# Power.net
KiCad netlist of a schematic drawn in Altium Designer
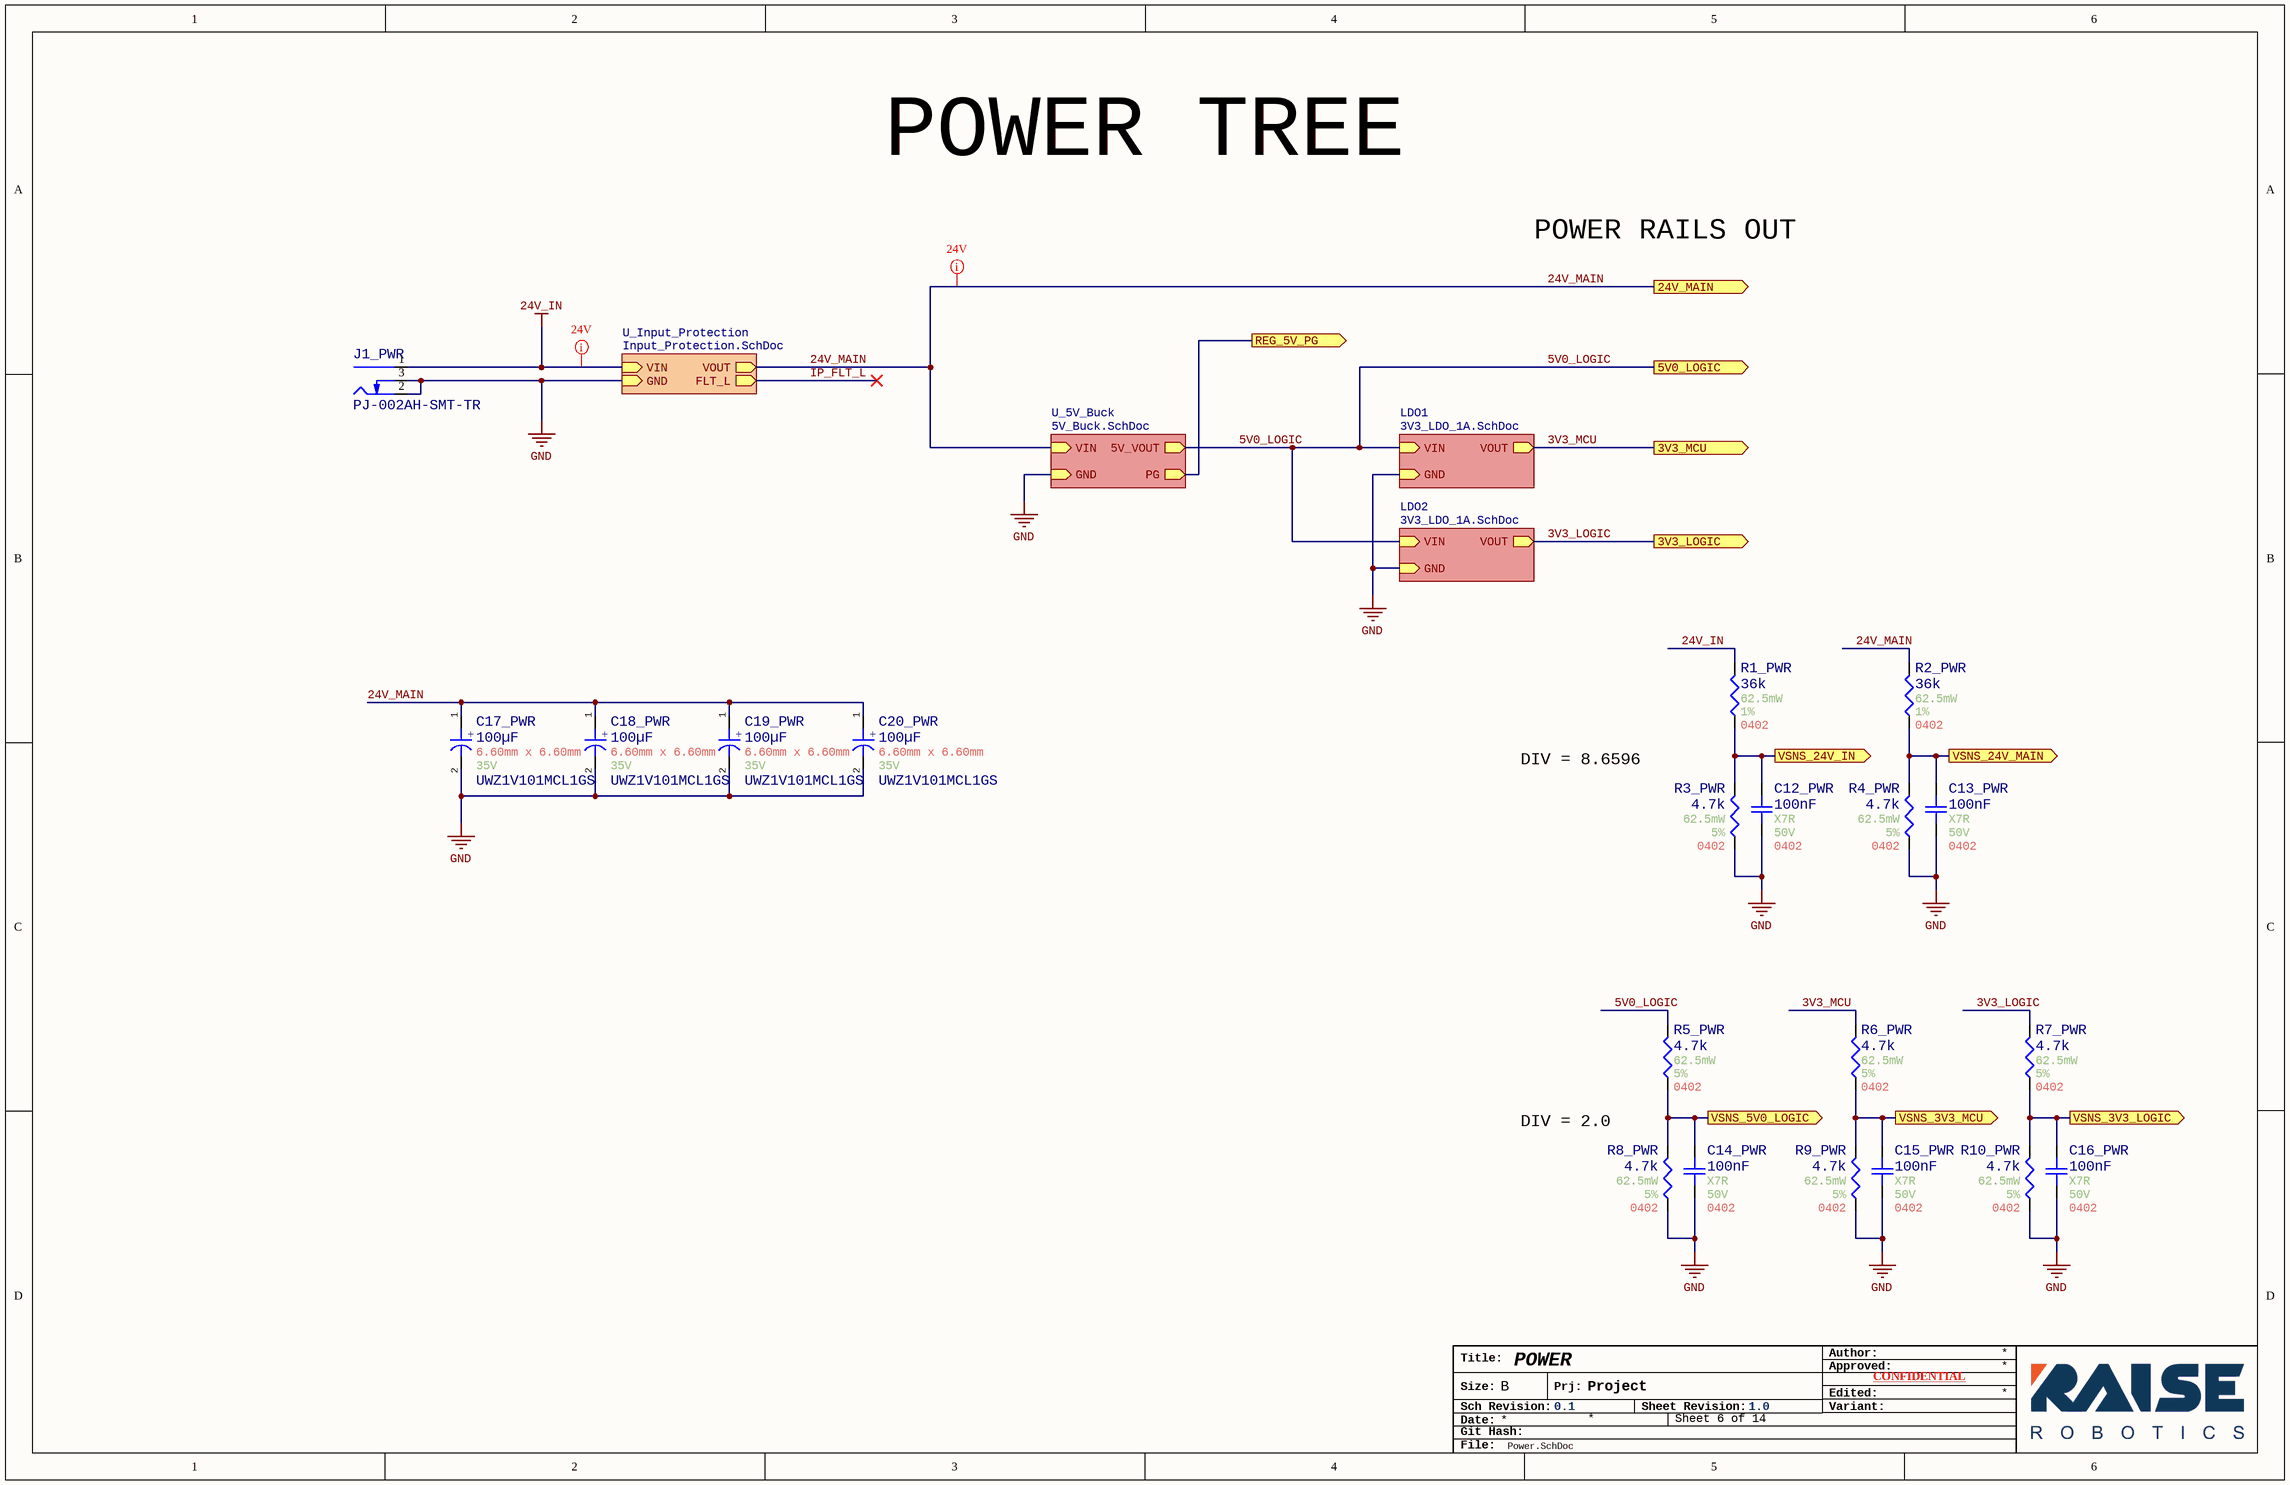
[diagram p0: Power.SchDoc]

(export (version "E")
  (design (tool "Eeschema 10.0.6"))
  (components
    (comp (ref "C12_PWR")
      (value "100nF")
      (footprint "Generic 0402 capacitor")
      (fields
        (field (name "TEMPERATURE COEFFICIENT") "X7R")
        (field (name "VOLTAGE RATING") "50V")
        (field (name "CASE/PACKAGE") "0402")
        (field (name "TOLERANCE") "10%")
        (field (name "Comment") "GRT155R71H104KE01D")
      )
      (libsource (lib "Raise Robotics") (part "Unpolarized Capacitor"))
    )
    (comp (ref "C13_PWR")
      (value "100nF")
      (footprint "Generic 0402 capacitor")
      (fields
        (field (name "TEMPERATURE COEFFICIENT") "X7R")
        (field (name "VOLTAGE RATING") "50V")
        (field (name "CASE/PACKAGE") "0402")
        (field (name "TOLERANCE") "10%")
        (field (name "Comment") "GRT155R71H104KE01D")
      )
      (libsource (lib "Raise Robotics") (part "Unpolarized Capacitor"))
    )
    (comp (ref "C14_PWR")
      (value "100nF")
      (footprint "Generic 0402 capacitor")
      (fields
        (field (name "TEMPERATURE COEFFICIENT") "X7R")
        (field (name "VOLTAGE RATING") "50V")
        (field (name "CASE/PACKAGE") "0402")
        (field (name "TOLERANCE") "10%")
        (field (name "Comment") "GRT155R71H104KE01D")
      )
      (libsource (lib "Raise Robotics") (part "Unpolarized Capacitor"))
    )
    (comp (ref "C15_PWR")
      (value "100nF")
      (footprint "Generic 0402 capacitor")
      (fields
        (field (name "TEMPERATURE COEFFICIENT") "X7R")
        (field (name "VOLTAGE RATING") "50V")
        (field (name "CASE/PACKAGE") "0402")
        (field (name "TOLERANCE") "10%")
        (field (name "Comment") "GRT155R71H104KE01D")
      )
      (libsource (lib "Raise Robotics") (part "Unpolarized Capacitor"))
    )
    (comp (ref "C16_PWR")
      (value "100nF")
      (footprint "Generic 0402 capacitor")
      (fields
        (field (name "TEMPERATURE COEFFICIENT") "X7R")
        (field (name "VOLTAGE RATING") "50V")
        (field (name "CASE/PACKAGE") "0402")
        (field (name "TOLERANCE") "10%")
        (field (name "Comment") "GRT155R71H104KE01D")
      )
      (libsource (lib "Raise Robotics") (part "Unpolarized Capacitor"))
    )
    (comp (ref "C17_PWR")
      (value "UWZ1V101MCL1GS")
      (footprint "UWZ1V101MCL1GS")
      (fields
        (field (name "ALTIUM_VALUE") "100µF")
        (field (name "CASE/PACKAGE") "6.60mm x 6.60mm")
        (field (name "VOLTAGE RATING") "35V")
      )
      (libsource (lib "Raise Robotics") (part "Polarized Capacitor Pin1+"))
    )
    (comp (ref "C18_PWR")
      (value "UWZ1V101MCL1GS")
      (footprint "UWZ1V101MCL1GS")
      (fields
        (field (name "ALTIUM_VALUE") "100µF")
        (field (name "CASE/PACKAGE") "6.60mm x 6.60mm")
        (field (name "VOLTAGE RATING") "35V")
      )
      (libsource (lib "Raise Robotics") (part "Polarized Capacitor Pin1+"))
    )
    (comp (ref "C19_PWR")
      (value "UWZ1V101MCL1GS")
      (footprint "UWZ1V101MCL1GS")
      (fields
        (field (name "ALTIUM_VALUE") "100µF")
        (field (name "CASE/PACKAGE") "6.60mm x 6.60mm")
        (field (name "VOLTAGE RATING") "35V")
      )
      (libsource (lib "Raise Robotics") (part "Polarized Capacitor Pin1+"))
    )
    (comp (ref "C20_PWR")
      (value "UWZ1V101MCL1GS")
      (footprint "UWZ1V101MCL1GS")
      (fields
        (field (name "ALTIUM_VALUE") "100µF")
        (field (name "CASE/PACKAGE") "6.60mm x 6.60mm")
        (field (name "VOLTAGE RATING") "35V")
      )
      (libsource (lib "Raise Robotics") (part "Polarized Capacitor Pin1+"))
    )
    (comp (ref "J1_PWR")
      (value "PJ-002AH-SMT-TR")
      (footprint "CUI PJ-002AH-SMT-TR")
      (description "CONN PWR JACK 2X5.5MM SOLDER")
      (fields (field (name "MANUFACTURER") "CUI Devices"))
      (libsource (lib "Celestial Altium Library - altium_library") (part "Barrel Connector"))
    )
    (comp (ref "R1_PWR")
      (value "36k")
      (footprint "Generic 0402 Resistor")
      (fields
        (field (name "POWER") "62.5mW")
        (field (name "TOLERANCE") "1%")
        (field (name "CASE/PACKAGE") "0402")
        (field (name "Comment") "AC0402FR-0736KL")
      )
      (libsource (lib "Raise Robotics") (part "Resistor"))
    )
    (comp (ref "R2_PWR")
      (value "36k")
      (footprint "Generic 0402 Resistor")
      (fields
        (field (name "POWER") "62.5mW")
        (field (name "TOLERANCE") "1%")
        (field (name "CASE/PACKAGE") "0402")
        (field (name "Comment") "AC0402FR-0736KL")
      )
      (libsource (lib "Raise Robotics") (part "Resistor"))
    )
    (comp (ref "R3_PWR")
      (value "4.7k")
      (footprint "Generic 0402 Resistor")
      (fields
        (field (name "POWER") "62.5mW")
        (field (name "TOLERANCE") "5%")
        (field (name "CASE/PACKAGE") "0402")
        (field (name "MANUFACTURER PART NUMBER") "Blank")
        (field (name "Comment") "WR04X472JTL")
      )
      (libsource (lib "Raise Robotics") (part "Resistor"))
    )
    (comp (ref "R4_PWR")
      (value "4.7k")
      (footprint "Generic 0402 Resistor")
      (fields
        (field (name "POWER") "62.5mW")
        (field (name "TOLERANCE") "5%")
        (field (name "CASE/PACKAGE") "0402")
        (field (name "MANUFACTURER PART NUMBER") "Blank")
        (field (name "Comment") "WR04X472JTL")
      )
      (libsource (lib "Raise Robotics") (part "Resistor"))
    )
    (comp (ref "R5_PWR")
      (value "4.7k")
      (footprint "Generic 0402 Resistor")
      (fields
        (field (name "POWER") "62.5mW")
        (field (name "TOLERANCE") "5%")
        (field (name "CASE/PACKAGE") "0402")
        (field (name "MANUFACTURER PART NUMBER") "Blank")
        (field (name "Comment") "WR04X472JTL")
      )
      (libsource (lib "Raise Robotics") (part "Resistor"))
    )
    (comp (ref "R6_PWR")
      (value "4.7k")
      (footprint "Generic 0402 Resistor")
      (fields
        (field (name "POWER") "62.5mW")
        (field (name "TOLERANCE") "5%")
        (field (name "CASE/PACKAGE") "0402")
        (field (name "MANUFACTURER PART NUMBER") "Blank")
        (field (name "Comment") "WR04X472JTL")
      )
      (libsource (lib "Raise Robotics") (part "Resistor"))
    )
    (comp (ref "R7_PWR")
      (value "4.7k")
      (footprint "Generic 0402 Resistor")
      (fields
        (field (name "POWER") "62.5mW")
        (field (name "TOLERANCE") "5%")
        (field (name "CASE/PACKAGE") "0402")
        (field (name "MANUFACTURER PART NUMBER") "Blank")
        (field (name "Comment") "WR04X472JTL")
      )
      (libsource (lib "Raise Robotics") (part "Resistor"))
    )
    (comp (ref "R8_PWR")
      (value "4.7k")
      (footprint "Generic 0402 Resistor")
      (fields
        (field (name "POWER") "62.5mW")
        (field (name "TOLERANCE") "5%")
        (field (name "CASE/PACKAGE") "0402")
        (field (name "MANUFACTURER PART NUMBER") "Blank")
        (field (name "Comment") "WR04X472JTL")
      )
      (libsource (lib "Raise Robotics") (part "Resistor"))
    )
    (comp (ref "R9_PWR")
      (value "4.7k")
      (footprint "Generic 0402 Resistor")
      (fields
        (field (name "POWER") "62.5mW")
        (field (name "TOLERANCE") "5%")
        (field (name "CASE/PACKAGE") "0402")
        (field (name "MANUFACTURER PART NUMBER") "Blank")
        (field (name "Comment") "WR04X472JTL")
      )
      (libsource (lib "Raise Robotics") (part "Resistor"))
    )
    (comp (ref "R10_PWR")
      (value "4.7k")
      (footprint "Generic 0402 Resistor")
      (fields
        (field (name "POWER") "62.5mW")
        (field (name "TOLERANCE") "5%")
        (field (name "CASE/PACKAGE") "0402")
        (field (name "MANUFACTURER PART NUMBER") "Blank")
        (field (name "Comment") "WR04X472JTL")
      )
      (libsource (lib "Raise Robotics") (part "Resistor"))
    )
  )
  (nets
    (net (code "1") (name "/3V3_LOGIC") (class "Default")
      (node (ref "R7_PWR") (pin "2") (pinfunction "2_2") (pintype "passive"))
    )
    (net (code "2") (name "/3V3_MCU") (class "Default")
      (node (ref "R6_PWR") (pin "2") (pinfunction "2_2") (pintype "passive"))
    )
    (net (code "3") (name "/5V0_LOGIC") (class "Default")
      (node (ref "R5_PWR") (pin "2") (pinfunction "2_2") (pintype "passive"))
    )
    (net (code "4") (name "/24V_MAIN") (class "Default")
      (node (ref "C17_PWR") (pin "1") (pinfunction "1_1") (pintype "passive"))
      (node (ref "C18_PWR") (pin "1") (pinfunction "1_1") (pintype "passive"))
      (node (ref "C19_PWR") (pin "1") (pinfunction "1_1") (pintype "passive"))
      (node (ref "C20_PWR") (pin "1") (pinfunction "1_1") (pintype "passive"))
      (node (ref "R2_PWR") (pin "2") (pinfunction "2_2") (pintype "passive"))
    )
    (net (code "7") (name "/VSNS_3V3_LOGIC") (class "Default")
      (node (ref "C16_PWR") (pin "1") (pinfunction "1_1") (pintype "passive"))
      (node (ref "R10_PWR") (pin "2") (pinfunction "2_2") (pintype "passive"))
      (node (ref "R7_PWR") (pin "1") (pinfunction "1_1") (pintype "passive"))
    )
    (net (code "8") (name "/VSNS_3V3_MCU") (class "Default")
      (node (ref "C15_PWR") (pin "1") (pinfunction "1_1") (pintype "passive"))
      (node (ref "R6_PWR") (pin "1") (pinfunction "1_1") (pintype "passive"))
      (node (ref "R9_PWR") (pin "2") (pinfunction "2_2") (pintype "passive"))
    )
    (net (code "9") (name "/VSNS_5V0_LOGIC") (class "Default")
      (node (ref "C14_PWR") (pin "1") (pinfunction "1_1") (pintype "passive"))
      (node (ref "R5_PWR") (pin "1") (pinfunction "1_1") (pintype "passive"))
      (node (ref "R8_PWR") (pin "2") (pinfunction "2_2") (pintype "passive"))
    )
    (net (code "10") (name "/VSNS_24V_IN") (class "Default")
      (node (ref "C12_PWR") (pin "1") (pinfunction "1_1") (pintype "passive"))
      (node (ref "R1_PWR") (pin "1") (pinfunction "1_1") (pintype "passive"))
      (node (ref "R3_PWR") (pin "2") (pinfunction "2_2") (pintype "passive"))
    )
    (net (code "11") (name "/VSNS_24V_MAIN") (class "Default")
      (node (ref "C13_PWR") (pin "1") (pinfunction "1_1") (pintype "passive"))
      (node (ref "R2_PWR") (pin "1") (pinfunction "1_1") (pintype "passive"))
      (node (ref "R4_PWR") (pin "2") (pinfunction "2_2") (pintype "passive"))
    )
    (net (code "12") (name "24V_IN") (class "Default")
      (node (ref "J1_PWR") (pin "1") (pinfunction "Centre_1") (pintype "passive"))
      (node (ref "R1_PWR") (pin "2") (pinfunction "2_2") (pintype "passive"))
    )
    (net (code "13") (name "GND") (class "Default")
      (node (ref "C12_PWR") (pin "2") (pinfunction "2_2") (pintype "passive"))
      (node (ref "C13_PWR") (pin "2") (pinfunction "2_2") (pintype "passive"))
      (node (ref "C14_PWR") (pin "2") (pinfunction "2_2") (pintype "passive"))
      (node (ref "C15_PWR") (pin "2") (pinfunction "2_2") (pintype "passive"))
      (node (ref "C16_PWR") (pin "2") (pinfunction "2_2") (pintype "passive"))
      (node (ref "C17_PWR") (pin "2") (pinfunction "2_2") (pintype "passive"))
      (node (ref "C18_PWR") (pin "2") (pinfunction "2_2") (pintype "passive"))
      (node (ref "C19_PWR") (pin "2") (pinfunction "2_2") (pintype "passive"))
      (node (ref "C20_PWR") (pin "2") (pinfunction "2_2") (pintype "passive"))
      (node (ref "J1_PWR") (pin "2") (pinfunction "Outer_2") (pintype "passive"))
      (node (ref "J1_PWR") (pin "3") (pinfunction "SW_3") (pintype "passive"))
      (node (ref "R10_PWR") (pin "1") (pinfunction "1_1") (pintype "passive"))
      (node (ref "R3_PWR") (pin "1") (pinfunction "1_1") (pintype "passive"))
      (node (ref "R4_PWR") (pin "1") (pinfunction "1_1") (pintype "passive"))
      (node (ref "R8_PWR") (pin "1") (pinfunction "1_1") (pintype "passive"))
      (node (ref "R9_PWR") (pin "1") (pinfunction "1_1") (pintype "passive"))
    )
  )
)
